# 02-Nucleo_Breakout.net
KiCad netlist of a schematic drawn in Altium Designer
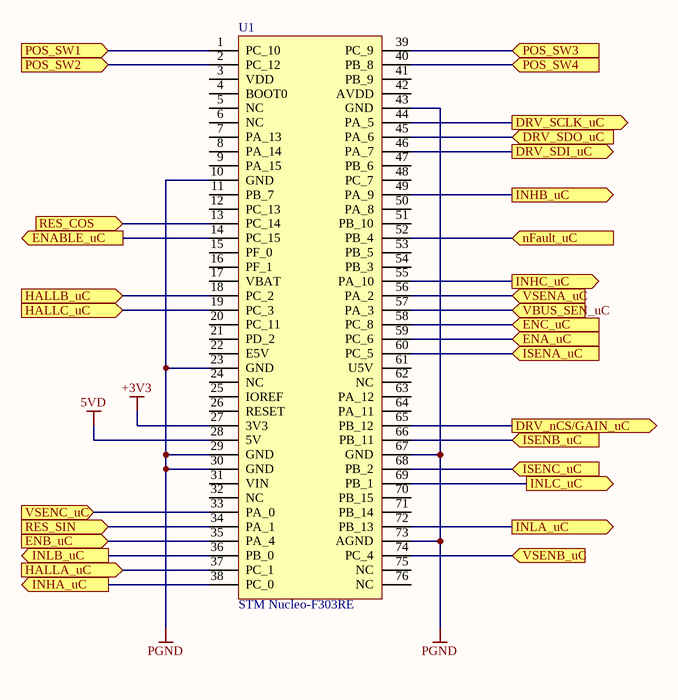
[diagram p0: 02-Nucleo_Breakout.SchDoc]

(export (version "E")
  (design (tool "Eeschema 10.0.6"))
  (components
    (comp (ref "U1")
      (value "STM Nucleo-F303RE")
      (footprint "Nucleo MORPHO CONNECTORS")
      (libsource (lib "driver_board_lib") (part "STM Nucleo-F303RE"))
    )
  )
  (nets
    (net (code "1") (name "+3V3") (class "Default")
      (node (ref "U1") (pin "27") (pinfunction "3V3_27") (pintype "passive"))
    )
    (net (code "2") (name "/DRV_SCLK_uC") (class "Default")
      (node (ref "U1") (pin "44") (pinfunction "PA_5_44") (pintype "passive"))
    )
    (net (code "3") (name "/DRV_SDI_uC") (class "Default")
      (node (ref "U1") (pin "46") (pinfunction "PA_7_46") (pintype "passive"))
    )
    (net (code "4") (name "/DRV_SDO_uC") (class "Default")
      (node (ref "U1") (pin "45") (pinfunction "PA_6_45") (pintype "passive"))
    )
    (net (code "5") (name "/DRV_nCS{slash}GAIN_uC") (class "Default")
      (node (ref "U1") (pin "65") (pinfunction "PB_12_65") (pintype "passive"))
    )
    (net (code "6") (name "/ENABLE_uC") (class "Default")
      (node (ref "U1") (pin "14") (pinfunction "PC_15_14") (pintype "passive"))
    )
    (net (code "7") (name "/ENA_uC") (class "Default")
      (node (ref "U1") (pin "59") (pinfunction "PC_6_59") (pintype "passive"))
    )
    (net (code "8") (name "/ENB_uC") (class "Default")
      (node (ref "U1") (pin "35") (pinfunction "PA_4_35") (pintype "passive"))
    )
    (net (code "9") (name "/ENC_uC") (class "Default")
      (node (ref "U1") (pin "58") (pinfunction "PC_8_58") (pintype "passive"))
    )
    (net (code "10") (name "/HALLA_uC") (class "Default")
      (node (ref "U1") (pin "37") (pinfunction "PC_1_37") (pintype "passive"))
    )
    (net (code "11") (name "/HALLB_uC") (class "Default")
      (node (ref "U1") (pin "18") (pinfunction "PC_2_18") (pintype "passive"))
    )
    (net (code "12") (name "/HALLC_uC") (class "Default")
      (node (ref "U1") (pin "19") (pinfunction "PC_3_19") (pintype "passive"))
    )
    (net (code "13") (name "/INHA_uC") (class "Default")
      (node (ref "U1") (pin "38") (pinfunction "PC_0_38") (pintype "passive"))
    )
    (net (code "14") (name "/INHB_uC") (class "Default")
      (node (ref "U1") (pin "49") (pinfunction "PA_9_49") (pintype "passive"))
    )
    (net (code "15") (name "/INHC_uC") (class "Default")
      (node (ref "U1") (pin "55") (pinfunction "PA_10_55") (pintype "passive"))
    )
    (net (code "16") (name "/INLA_uC") (class "Default")
      (node (ref "U1") (pin "72") (pinfunction "PB_13_72") (pintype "passive"))
    )
    (net (code "17") (name "/INLB_uC") (class "Default")
      (node (ref "U1") (pin "36") (pinfunction "PB_0_36") (pintype "passive"))
    )
    (net (code "18") (name "/INLC_uC") (class "Default")
      (node (ref "U1") (pin "69") (pinfunction "PB_1_69") (pintype "passive"))
    )
    (net (code "19") (name "/ISENA_uC") (class "Default")
      (node (ref "U1") (pin "60") (pinfunction "PC_5_60") (pintype "passive"))
    )
    (net (code "20") (name "/ISENB_uC") (class "Default")
      (node (ref "U1") (pin "66") (pinfunction "PB_11_66") (pintype "passive"))
    )
    (net (code "21") (name "/ISENC_uC") (class "Default")
      (node (ref "U1") (pin "68") (pinfunction "PB_2_68") (pintype "passive"))
    )
    (net (code "22") (name "/POS_SW1") (class "Default")
      (node (ref "U1") (pin "1") (pinfunction "PC_10_1") (pintype "passive"))
    )
    (net (code "23") (name "/POS_SW2") (class "Default")
      (node (ref "U1") (pin "2") (pinfunction "PC_12_2") (pintype "passive"))
    )
    (net (code "24") (name "/POS_SW3") (class "Default")
      (node (ref "U1") (pin "39") (pinfunction "PC_9_39") (pintype "passive"))
    )
    (net (code "25") (name "/POS_SW4") (class "Default")
      (node (ref "U1") (pin "40") (pinfunction "PB_8_40") (pintype "passive"))
    )
    (net (code "26") (name "/RES_COS") (class "Default")
      (node (ref "U1") (pin "13") (pinfunction "PC_14_13") (pintype "passive"))
    )
    (net (code "27") (name "/RES_SIN") (class "Default")
      (node (ref "U1") (pin "34") (pinfunction "PA_1_34") (pintype "passive"))
    )
    (net (code "28") (name "/VBUS_SEN_uC") (class "Default")
      (node (ref "U1") (pin "57") (pinfunction "PA_3_57") (pintype "passive"))
    )
    (net (code "29") (name "/VSENA_uC") (class "Default")
      (node (ref "U1") (pin "56") (pinfunction "PA_2_56") (pintype "passive"))
    )
    (net (code "30") (name "/VSENB_uC") (class "Default")
      (node (ref "U1") (pin "74") (pinfunction "PC_4_74") (pintype "passive"))
    )
    (net (code "31") (name "/VSENC_uC") (class "Default")
      (node (ref "U1") (pin "33") (pinfunction "PA_0_33") (pintype "passive"))
    )
    (net (code "32") (name "/nFault_uC") (class "Default")
      (node (ref "U1") (pin "52") (pinfunction "PB_4_52") (pintype "passive"))
    )
    (net (code "33") (name "5VD") (class "Default")
      (node (ref "U1") (pin "28") (pinfunction "5V_28") (pintype "passive"))
    )
    (net (code "34") (name "PGND") (class "Default")
      (node (ref "U1") (pin "10") (pinfunction "GND_10") (pintype "passive"))
      (node (ref "U1") (pin "23") (pinfunction "GND_23") (pintype "passive"))
      (node (ref "U1") (pin "29") (pinfunction "GND_29") (pintype "passive"))
      (node (ref "U1") (pin "30") (pinfunction "GND_30") (pintype "passive"))
      (node (ref "U1") (pin "43") (pinfunction "GND_43") (pintype "passive"))
      (node (ref "U1") (pin "67") (pinfunction "GND_67") (pintype "passive"))
      (node (ref "U1") (pin "73") (pinfunction "AGND_73") (pintype "passive"))
    )
    (net (code "35") (name "unconnected-(U1-AVDD-Pad42)") (class "Default")
      (node (ref "U1") (pin "42") (pinfunction "AVDD_42") (pintype "passive"))
    )
    (net (code "36") (name "unconnected-(U1-BOOT0-Pad4)") (class "Default")
      (node (ref "U1") (pin "4") (pinfunction "BOOT0_4") (pintype "passive"))
    )
    (net (code "37") (name "unconnected-(U1-E5V-Pad22)") (class "Default")
      (node (ref "U1") (pin "22") (pinfunction "E5V_22") (pintype "passive"))
    )
    (net (code "38") (name "unconnected-(U1-IOREF-Pad25)") (class "Default")
      (node (ref "U1") (pin "25") (pinfunction "IOREF_25") (pintype "passive"))
    )
    (net (code "39") (name "unconnected-(U1-NC-Pad5)") (class "Default")
      (node (ref "U1") (pin "5") (pinfunction "NC_5") (pintype "passive"))
    )
    (net (code "40") (name "unconnected-(U1-NC-Pad6)") (class "Default")
      (node (ref "U1") (pin "6") (pinfunction "NC_6") (pintype "passive"))
    )
    (net (code "41") (name "unconnected-(U1-NC-Pad24)") (class "Default")
      (node (ref "U1") (pin "24") (pinfunction "NC_24") (pintype "passive"))
    )
    (net (code "42") (name "unconnected-(U1-NC-Pad32)") (class "Default")
      (node (ref "U1") (pin "32") (pinfunction "NC_32") (pintype "passive"))
    )
    (net (code "43") (name "unconnected-(U1-NC-Pad62)") (class "Default")
      (node (ref "U1") (pin "62") (pinfunction "NC_62") (pintype "passive"))
    )
    (net (code "44") (name "unconnected-(U1-NC-Pad75)") (class "Default")
      (node (ref "U1") (pin "75") (pinfunction "NC_75") (pintype "passive"))
    )
    (net (code "45") (name "unconnected-(U1-NC-Pad76)") (class "Default")
      (node (ref "U1") (pin "76") (pinfunction "NC_76") (pintype "passive"))
    )
    (net (code "46") (name "unconnected-(U1-PA_8-Pad50)") (class "Default")
      (node (ref "U1") (pin "50") (pinfunction "PA_8_50") (pintype "passive"))
    )
    (net (code "47") (name "unconnected-(U1-PA_11-Pad64)") (class "Default")
      (node (ref "U1") (pin "64") (pinfunction "PA_11_64") (pintype "passive"))
    )
    (net (code "48") (name "unconnected-(U1-PA_12-Pad63)") (class "Default")
      (node (ref "U1") (pin "63") (pinfunction "PA_12_63") (pintype "passive"))
    )
    (net (code "49") (name "unconnected-(U1-PA_13-Pad7)") (class "Default")
      (node (ref "U1") (pin "7") (pinfunction "PA_13_7") (pintype "passive"))
    )
    (net (code "50") (name "unconnected-(U1-PA_14-Pad8)") (class "Default")
      (node (ref "U1") (pin "8") (pinfunction "PA_14_8") (pintype "passive"))
    )
    (net (code "51") (name "unconnected-(U1-PA_15-Pad9)") (class "Default")
      (node (ref "U1") (pin "9") (pinfunction "PA_15_9") (pintype "passive"))
    )
    (net (code "52") (name "unconnected-(U1-PB_3-Pad54)") (class "Default")
      (node (ref "U1") (pin "54") (pinfunction "PB_3_54") (pintype "passive"))
    )
    (net (code "53") (name "unconnected-(U1-PB_5-Pad53)") (class "Default")
      (node (ref "U1") (pin "53") (pinfunction "PB_5_53") (pintype "passive"))
    )
    (net (code "54") (name "unconnected-(U1-PB_6-Pad47)") (class "Default")
      (node (ref "U1") (pin "47") (pinfunction "PB_6_47") (pintype "passive"))
    )
    (net (code "55") (name "unconnected-(U1-PB_7-Pad11)") (class "Default")
      (node (ref "U1") (pin "11") (pinfunction "PB_7_11") (pintype "passive"))
    )
    (net (code "56") (name "unconnected-(U1-PB_9-Pad41)") (class "Default")
      (node (ref "U1") (pin "41") (pinfunction "PB_9_41") (pintype "passive"))
    )
    (net (code "57") (name "unconnected-(U1-PB_10-Pad51)") (class "Default")
      (node (ref "U1") (pin "51") (pinfunction "PB_10_51") (pintype "passive"))
    )
    (net (code "58") (name "unconnected-(U1-PB_14-Pad71)") (class "Default")
      (node (ref "U1") (pin "71") (pinfunction "PB_14_71") (pintype "passive"))
    )
    (net (code "59") (name "unconnected-(U1-PB_15-Pad70)") (class "Default")
      (node (ref "U1") (pin "70") (pinfunction "PB_15_70") (pintype "passive"))
    )
    (net (code "60") (name "unconnected-(U1-PC_7-Pad48)") (class "Default")
      (node (ref "U1") (pin "48") (pinfunction "PC_7_48") (pintype "passive"))
    )
    (net (code "61") (name "unconnected-(U1-PC_11-Pad20)") (class "Default")
      (node (ref "U1") (pin "20") (pinfunction "PC_11_20") (pintype "passive"))
    )
    (net (code "62") (name "unconnected-(U1-PC_13-Pad12)") (class "Default")
      (node (ref "U1") (pin "12") (pinfunction "PC_13_12") (pintype "passive"))
    )
    (net (code "63") (name "unconnected-(U1-PD_2-Pad21)") (class "Default")
      (node (ref "U1") (pin "21") (pinfunction "PD_2_21") (pintype "passive"))
    )
    (net (code "64") (name "unconnected-(U1-PF_0-Pad15)") (class "Default")
      (node (ref "U1") (pin "15") (pinfunction "PF_0_15") (pintype "passive"))
    )
    (net (code "65") (name "unconnected-(U1-PF_1-Pad16)") (class "Default")
      (node (ref "U1") (pin "16") (pinfunction "PF_1_16") (pintype "passive"))
    )
    (net (code "66") (name "unconnected-(U1-RESET-Pad26)") (class "Default")
      (node (ref "U1") (pin "26") (pinfunction "RESET_26") (pintype "passive"))
    )
    (net (code "67") (name "unconnected-(U1-U5V-Pad61)") (class "Default")
      (node (ref "U1") (pin "61") (pinfunction "U5V_61") (pintype "passive"))
    )
    (net (code "68") (name "unconnected-(U1-VBAT-Pad17)") (class "Default")
      (node (ref "U1") (pin "17") (pinfunction "VBAT_17") (pintype "passive"))
    )
    (net (code "69") (name "unconnected-(U1-VDD-Pad3)") (class "Default")
      (node (ref "U1") (pin "3") (pinfunction "VDD_3") (pintype "passive"))
    )
    (net (code "70") (name "unconnected-(U1-VIN-Pad31)") (class "Default")
      (node (ref "U1") (pin "31") (pinfunction "VIN_31") (pintype "passive"))
    )
  )
)
